# LED_Module_v2_SCH.net
KiCad netlist of a schematic drawn in Altium Designer
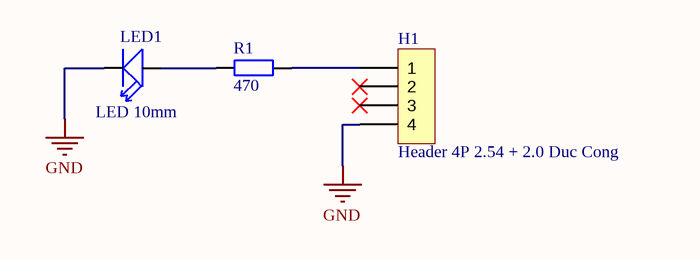
[diagram p0: LED Module_v2_SCH.schdoc]

(export (version "E")
  (design (tool "Eeschema 10.0.6"))
  (components
    (comp (ref "H1")
      (value "Header 4P 2.54 + 2.0 Duc Cong")
      (footprint "Header 4P DC 2.54 + 2.0")
      (description "Cắm")
      (libsource (lib "namnt_Lib") (part "Header 4P 2.54 + 2.0 Duc Cong"))
    )
    (comp (ref "LED1")
      (value "LED 10mm")
      (footprint "LED2-2.54-D10MM")
      (description "304090142")
      (fields (field (name "MP") "DIP-LED-BLUE-BLUE-10MM(2P-D10MM)"))
      (libsource (lib "namnt_Lib") (part "LED 10mm"))
    )
    (comp (ref "R1")
      (value "470")
      (footprint "tro smd 0603")
      (description "Dán")
      (libsource (lib "namnt_Lib") (part "Tro 0603 5% 330R"))
    )
  )
  (nets
    (net (code "1") (name "GND") (class "Default")
      (node (ref "H1") (pin "4") (pinfunction "4_4") (pintype "passive"))
      (node (ref "LED1") (pin "NEG") (pinfunction "NEG_NEG") (pintype "passive"))
    )
    (net (code "2") (name "Net-(H1-Pad1)") (class "Default")
      (node (ref "H1") (pin "1") (pinfunction "1_1") (pintype "passive"))
      (node (ref "R1") (pin "2") (pinfunction "2_2") (pintype "passive"))
    )
    (net (code "3") (name "Net-(LED1-PadPOS)") (class "Default")
      (node (ref "LED1") (pin "POS") (pinfunction "POS_POS") (pintype "passive"))
      (node (ref "R1") (pin "1") (pinfunction "1_1") (pintype "passive"))
    )
    (net (code "4") (name "unconnected-(H1-Pad2)") (class "Default")
      (node (ref "H1") (pin "2") (pinfunction "2_2") (pintype "passive+no_connect"))
    )
    (net (code "5") (name "unconnected-(H1-Pad3)") (class "Default")
      (node (ref "H1") (pin "3") (pinfunction "3_3") (pintype "passive+no_connect"))
    )
  )
)
